# eMMC.net
KiCad netlist of a schematic drawn in Altium Designer
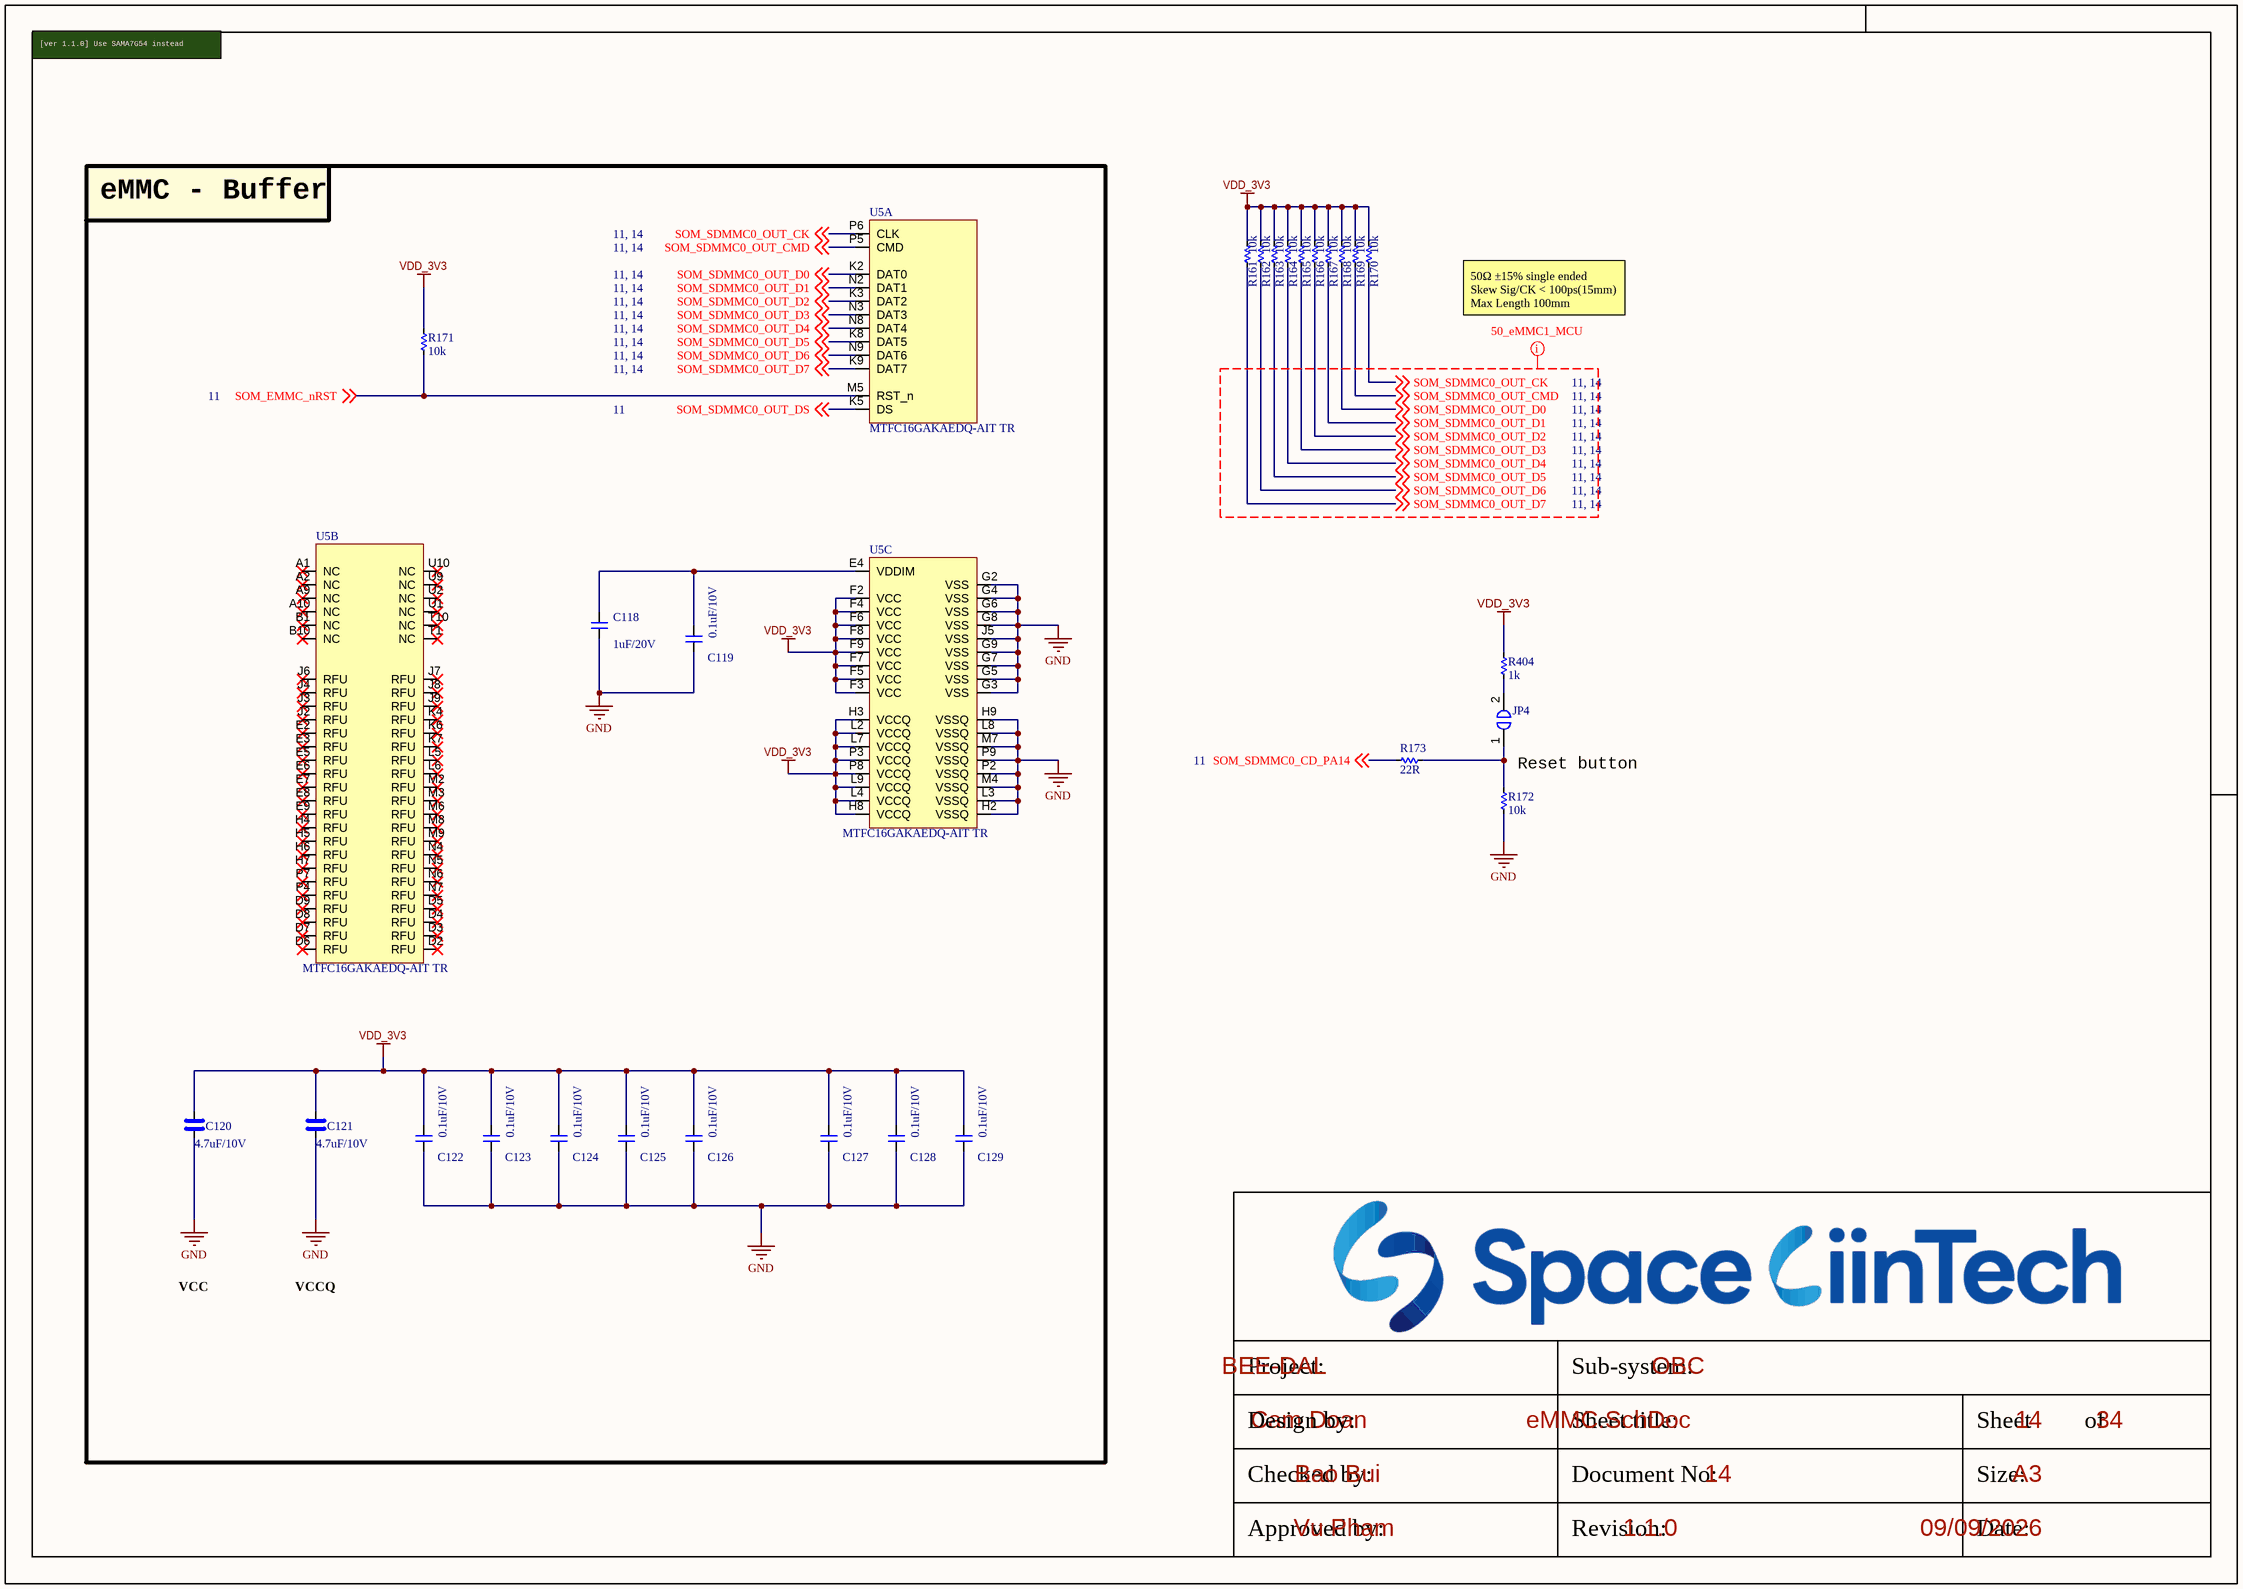
[diagram p0: eMMC.SchDoc]

(export (version "E")
  (design (tool "Eeschema 10.0.6"))
  (components
    (comp (ref "C118")
      (value "1uF/20V")
      (footprint "CAP_C_1005X50_L")
      (description "CAP CHIP")
      (libsource (lib "IFBschelib") (part "_CAP_C_2"))
    )
    (comp (ref "C119")
      (value "0.1uF/10V")
      (footprint "CAP_C_1005X50_L")
      (description "CAP")
      (libsource (lib "LABLIB") (part "_CAP_C_2"))
    )
    (comp (ref "C120")
      (value "4.7uF/10V")
      (footprint "CAP_C_1005X50_L")
      (description "CAP")
      (libsource (lib "LABLIB") (part "_CAP_C_High_2"))
    )
    (comp (ref "C121")
      (value "4.7uF/10V")
      (footprint "CAP_C_1005X50_L")
      (description "CAP")
      (libsource (lib "LABLIB") (part "_CAP_C_High_2"))
    )
    (comp (ref "C122")
      (value "0.1uF/10V")
      (footprint "CAP_C_1005X50_L")
      (description "CAP")
      (libsource (lib "LABLIB") (part "_CAP_C_2"))
    )
    (comp (ref "C123")
      (value "0.1uF/10V")
      (footprint "CAP_C_1005X50_L")
      (description "CAP")
      (libsource (lib "LABLIB") (part "_CAP_C_2"))
    )
    (comp (ref "C124")
      (value "0.1uF/10V")
      (footprint "CAP_C_1005X50_L")
      (description "CAP")
      (libsource (lib "LABLIB") (part "_CAP_C_2"))
    )
    (comp (ref "C125")
      (value "0.1uF/10V")
      (footprint "CAP_C_1005X50_L")
      (description "CAP")
      (libsource (lib "LABLIB") (part "_CAP_C_2"))
    )
    (comp (ref "C126")
      (value "0.1uF/10V")
      (footprint "CAP_C_1005X50_L")
      (description "CAP")
      (libsource (lib "LABLIB") (part "_CAP_C_2"))
    )
    (comp (ref "C127")
      (value "0.1uF/10V")
      (footprint "CAP_C_1005X50_L")
      (description "CAP")
      (libsource (lib "LABLIB") (part "_CAP_C_2"))
    )
    (comp (ref "C128")
      (value "0.1uF/10V")
      (footprint "CAP_C_1005X50_L")
      (description "CAP")
      (libsource (lib "LABLIB") (part "_CAP_C_2"))
    )
    (comp (ref "C129")
      (value "0.1uF/10V")
      (footprint "CAP_C_1005X50_L")
      (description "CAP")
      (libsource (lib "LABLIB") (part "_CAP_C_2"))
    )
    (comp (ref "JP4") (value "~") (footprint "JUMPER_1608") (libsource (lib "LABLIB") (part "JUMPER_1_1")))
    (comp (ref "R161")
      (value "10k")
      (footprint "RES_C_1005x30_L")
      (description "RES")
      (libsource (lib "LABLIB") (part "_RES_B_2"))
    )
    (comp (ref "R162")
      (value "10k")
      (footprint "RES_C_1005x30_L")
      (description "RES")
      (libsource (lib "LABLIB") (part "_RES_B_2"))
    )
    (comp (ref "R163")
      (value "10k")
      (footprint "RES_C_1005x30_L")
      (description "RES")
      (libsource (lib "LABLIB") (part "_RES_B_2"))
    )
    (comp (ref "R164")
      (value "10k")
      (footprint "RES_C_1005x30_L")
      (description "RES")
      (libsource (lib "LABLIB") (part "_RES_B_2"))
    )
    (comp (ref "R165")
      (value "10k")
      (footprint "RES_C_1005x30_L")
      (description "RES")
      (libsource (lib "LABLIB") (part "_RES_B_2"))
    )
    (comp (ref "R166")
      (value "10k")
      (footprint "RES_C_1005x30_L")
      (description "RES")
      (libsource (lib "LABLIB") (part "_RES_B_2"))
    )
    (comp (ref "R167")
      (value "10k")
      (footprint "RES_C_1005x30_L")
      (description "RES")
      (libsource (lib "LABLIB") (part "_RES_B_2"))
    )
    (comp (ref "R168")
      (value "10k")
      (footprint "RES_C_1005x30_L")
      (description "RES")
      (libsource (lib "LABLIB") (part "_RES_B_2"))
    )
    (comp (ref "R169")
      (value "10k")
      (footprint "RES_C_1005x30_L")
      (description "RES")
      (libsource (lib "LABLIB") (part "_RES_B_2"))
    )
    (comp (ref "R170")
      (value "10k")
      (footprint "RES_C_1005x30_L")
      (description "RES")
      (libsource (lib "LABLIB") (part "_RES_B_2"))
    )
    (comp (ref "R171")
      (value "10k")
      (footprint "RES_C_1005x30_L")
      (description "RES")
      (libsource (lib "LABLIB") (part "_RES_B_2"))
    )
    (comp (ref "R172")
      (value "10k")
      (footprint "RES_C_1005x30_L")
      (description "RES")
      (libsource (lib "LABLIB") (part "_RES_B_2"))
    )
    (comp (ref "R173")
      (value "22R")
      (footprint "RES_C_1005x30_L")
      (description "RES")
      (libsource (lib "LABLIB") (part "_RES_B_2"))
    )
    (comp (ref "R404")
      (value "1k")
      (footprint "RES_C_1005x30_L")
      (description "RES")
      (libsource (lib "LABLIB") (part "_RES_B_2"))
    )
    (comp (ref "U5")
      (value "MTFC16GAKAEDQ-AIT TR")
      (footprint "BGA_100_C_100P_10X17_1400X1800X150")
      (libsource (lib "LABLIB") (part "IC_eMMC_MTFC16GAKAEDQ-AIT TR"))
    )
  )
  (nets
    (net (code "1") (name "GND") (class "Default")
      (node (ref "C118") (pin "1") (pinfunction "1_1") (pintype "passive"))
      (node (ref "C119") (pin "1") (pinfunction "1_1") (pintype "passive"))
      (node (ref "C120") (pin "1") (pinfunction "1_1") (pintype "passive"))
      (node (ref "C121") (pin "1") (pinfunction "1_1") (pintype "passive"))
      (node (ref "C122") (pin "1") (pinfunction "1_1") (pintype "passive"))
      (node (ref "C123") (pin "1") (pinfunction "1_1") (pintype "passive"))
      (node (ref "C124") (pin "1") (pinfunction "1_1") (pintype "passive"))
      (node (ref "C125") (pin "1") (pinfunction "1_1") (pintype "passive"))
      (node (ref "C126") (pin "1") (pinfunction "1_1") (pintype "passive"))
      (node (ref "C127") (pin "1") (pinfunction "1_1") (pintype "passive"))
      (node (ref "C128") (pin "1") (pinfunction "1_1") (pintype "passive"))
      (node (ref "C129") (pin "1") (pinfunction "1_1") (pintype "passive"))
      (node (ref "R172") (pin "1") (pinfunction "1_1") (pintype "passive"))
      (node (ref "U5") (pin "G2") (pinfunction "VSS_G2") (pintype "passive"))
      (node (ref "U5") (pin "G3") (pinfunction "VSS_G3") (pintype "passive"))
      (node (ref "U5") (pin "G4") (pinfunction "VSS_G4") (pintype "passive"))
      (node (ref "U5") (pin "G5") (pinfunction "VSS_G5") (pintype "passive"))
      (node (ref "U5") (pin "G6") (pinfunction "VSS_G6") (pintype "passive"))
      (node (ref "U5") (pin "G7") (pinfunction "VSS_G7") (pintype "passive"))
      (node (ref "U5") (pin "G8") (pinfunction "VSS_G8") (pintype "passive"))
      (node (ref "U5") (pin "G9") (pinfunction "VSS_G9") (pintype "passive"))
      (node (ref "U5") (pin "H2") (pinfunction "VSSQ_H2") (pintype "passive"))
      (node (ref "U5") (pin "H9") (pinfunction "VSSQ_H9") (pintype "passive"))
      (node (ref "U5") (pin "J5") (pinfunction "VSS_J5") (pintype "passive"))
      (node (ref "U5") (pin "L3") (pinfunction "VSSQ_L3") (pintype "passive"))
      (node (ref "U5") (pin "L8") (pinfunction "VSSQ_L8") (pintype "passive"))
      (node (ref "U5") (pin "M4") (pinfunction "VSSQ_M4") (pintype "passive"))
      (node (ref "U5") (pin "M7") (pinfunction "VSSQ_M7") (pintype "passive"))
      (node (ref "U5") (pin "P2") (pinfunction "VSSQ_P2") (pintype "passive"))
      (node (ref "U5") (pin "P9") (pinfunction "VSSQ_P9") (pintype "passive"))
    )
    (net (code "2") (name "Net-(JP4-Pad1)") (class "Default")
      (node (ref "JP4") (pin "1") (pinfunction "1_1") (pintype "passive"))
      (node (ref "R172") (pin "2") (pinfunction "2_2") (pintype "passive"))
      (node (ref "R173") (pin "2") (pinfunction "2_2") (pintype "passive"))
    )
    (net (code "3") (name "Net-(JP4-Pad2)") (class "Default")
      (node (ref "JP4") (pin "2") (pinfunction "2_2") (pintype "passive"))
      (node (ref "R404") (pin "1") (pinfunction "1_1") (pintype "passive"))
    )
    (net (code "4") (name "Net-(U5C-VDDIM)") (class "Default")
      (node (ref "C118") (pin "2") (pinfunction "2_2") (pintype "passive"))
      (node (ref "C119") (pin "2") (pinfunction "2_2") (pintype "passive"))
      (node (ref "U5") (pin "E4") (pinfunction "VDDIM_E4") (pintype "passive"))
    )
    (net (code "5") (name "SOM_EMMC_nRST") (class "Default")
      (node (ref "R171") (pin "1") (pinfunction "1_1") (pintype "passive"))
      (node (ref "U5") (pin "M5") (pinfunction "RST_n_M5") (pintype "passive"))
    )
    (net (code "6") (name "SOM_SDMMC0_CD_PA14") (class "Default")
      (node (ref "R173") (pin "1") (pinfunction "1_1") (pintype "passive"))
    )
    (net (code "7") (name "SOM_SDMMC0_OUT_CK") (class "Default")
      (node (ref "R170") (pin "1") (pinfunction "1_1") (pintype "passive"))
      (node (ref "U5") (pin "P6") (pinfunction "CLK_P6") (pintype "passive"))
    )
    (net (code "8") (name "SOM_SDMMC0_OUT_CMD") (class "Default")
      (node (ref "R169") (pin "1") (pinfunction "1_1") (pintype "passive"))
      (node (ref "U5") (pin "P5") (pinfunction "CMD_P5") (pintype "passive"))
    )
    (net (code "9") (name "SOM_SDMMC0_OUT_D0") (class "Default")
      (node (ref "R168") (pin "1") (pinfunction "1_1") (pintype "passive"))
      (node (ref "U5") (pin "K2") (pinfunction "DAT0_K2") (pintype "passive"))
    )
    (net (code "10") (name "SOM_SDMMC0_OUT_D1") (class "Default")
      (node (ref "R167") (pin "1") (pinfunction "1_1") (pintype "passive"))
      (node (ref "U5") (pin "N2") (pinfunction "DAT1_N2") (pintype "passive"))
    )
    (net (code "11") (name "SOM_SDMMC0_OUT_D2") (class "Default")
      (node (ref "R166") (pin "1") (pinfunction "1_1") (pintype "passive"))
      (node (ref "U5") (pin "K3") (pinfunction "DAT2_K3") (pintype "passive"))
    )
    (net (code "12") (name "SOM_SDMMC0_OUT_D3") (class "Default")
      (node (ref "R165") (pin "1") (pinfunction "1_1") (pintype "passive"))
      (node (ref "U5") (pin "N3") (pinfunction "DAT3_N3") (pintype "passive"))
    )
    (net (code "13") (name "SOM_SDMMC0_OUT_D4") (class "Default")
      (node (ref "R164") (pin "1") (pinfunction "1_1") (pintype "passive"))
      (node (ref "U5") (pin "N8") (pinfunction "DAT4_N8") (pintype "passive"))
    )
    (net (code "14") (name "SOM_SDMMC0_OUT_D5") (class "Default")
      (node (ref "R163") (pin "1") (pinfunction "1_1") (pintype "passive"))
      (node (ref "U5") (pin "K8") (pinfunction "DAT5_K8") (pintype "passive"))
    )
    (net (code "15") (name "SOM_SDMMC0_OUT_D6") (class "Default")
      (node (ref "R162") (pin "1") (pinfunction "1_1") (pintype "passive"))
      (node (ref "U5") (pin "N9") (pinfunction "DAT6_N9") (pintype "passive"))
    )
    (net (code "16") (name "SOM_SDMMC0_OUT_D7") (class "Default")
      (node (ref "R161") (pin "1") (pinfunction "1_1") (pintype "passive"))
      (node (ref "U5") (pin "K9") (pinfunction "DAT7_K9") (pintype "passive"))
    )
    (net (code "17") (name "SOM_SDMMC0_OUT_DS") (class "Default")
      (node (ref "U5") (pin "K5") (pinfunction "DS_K5") (pintype "passive"))
    )
    (net (code "18") (name "VDD_3V3") (class "Default")
      (node (ref "C120") (pin "2") (pinfunction "2_2") (pintype "passive"))
      (node (ref "C121") (pin "2") (pinfunction "2_2") (pintype "passive"))
      (node (ref "C122") (pin "2") (pinfunction "2_2") (pintype "passive"))
      (node (ref "C123") (pin "2") (pinfunction "2_2") (pintype "passive"))
      (node (ref "C124") (pin "2") (pinfunction "2_2") (pintype "passive"))
      (node (ref "C125") (pin "2") (pinfunction "2_2") (pintype "passive"))
      (node (ref "C126") (pin "2") (pinfunction "2_2") (pintype "passive"))
      (node (ref "C127") (pin "2") (pinfunction "2_2") (pintype "passive"))
      (node (ref "C128") (pin "2") (pinfunction "2_2") (pintype "passive"))
      (node (ref "C129") (pin "2") (pinfunction "2_2") (pintype "passive"))
      (node (ref "R161") (pin "2") (pinfunction "2_2") (pintype "passive"))
      (node (ref "R162") (pin "2") (pinfunction "2_2") (pintype "passive"))
      (node (ref "R163") (pin "2") (pinfunction "2_2") (pintype "passive"))
      (node (ref "R164") (pin "2") (pinfunction "2_2") (pintype "passive"))
      (node (ref "R165") (pin "2") (pinfunction "2_2") (pintype "passive"))
      (node (ref "R166") (pin "2") (pinfunction "2_2") (pintype "passive"))
      (node (ref "R167") (pin "2") (pinfunction "2_2") (pintype "passive"))
      (node (ref "R168") (pin "2") (pinfunction "2_2") (pintype "passive"))
      (node (ref "R169") (pin "2") (pinfunction "2_2") (pintype "passive"))
      (node (ref "R170") (pin "2") (pinfunction "2_2") (pintype "passive"))
      (node (ref "R171") (pin "2") (pinfunction "2_2") (pintype "passive"))
      (node (ref "R404") (pin "2") (pinfunction "2_2") (pintype "passive"))
      (node (ref "U5") (pin "F2") (pinfunction "VCC_F2") (pintype "passive"))
      (node (ref "U5") (pin "F3") (pinfunction "VCC_F3") (pintype "passive"))
      (node (ref "U5") (pin "F4") (pinfunction "VCC_F4") (pintype "passive"))
      (node (ref "U5") (pin "F5") (pinfunction "VCC_F5") (pintype "passive"))
      (node (ref "U5") (pin "F6") (pinfunction "VCC_F6") (pintype "passive"))
      (node (ref "U5") (pin "F7") (pinfunction "VCC_F7") (pintype "passive"))
      (node (ref "U5") (pin "F8") (pinfunction "VCC_F8") (pintype "passive"))
      (node (ref "U5") (pin "F9") (pinfunction "VCC_F9") (pintype "passive"))
      (node (ref "U5") (pin "H3") (pinfunction "VCCQ_H3") (pintype "passive"))
      (node (ref "U5") (pin "H8") (pinfunction "VCCQ_H8") (pintype "passive"))
      (node (ref "U5") (pin "L2") (pinfunction "VCCQ_L2") (pintype "passive"))
      (node (ref "U5") (pin "L4") (pinfunction "VCCQ_L4") (pintype "passive"))
      (node (ref "U5") (pin "L7") (pinfunction "VCCQ_L7") (pintype "passive"))
      (node (ref "U5") (pin "L9") (pinfunction "VCCQ_L9") (pintype "passive"))
      (node (ref "U5") (pin "P3") (pinfunction "VCCQ_P3") (pintype "passive"))
      (node (ref "U5") (pin "P8") (pinfunction "VCCQ_P8") (pintype "passive"))
    )
    (net (code "19") (name "unconnected-(U5B-NC-PadA1)") (class "Default")
      (node (ref "U5") (pin "A1") (pinfunction "NC_A1") (pintype "passive+no_connect"))
    )
    (net (code "20") (name "unconnected-(U5B-NC-PadA2)") (class "Default")
      (node (ref "U5") (pin "A2") (pinfunction "NC_A2") (pintype "passive+no_connect"))
    )
    (net (code "21") (name "unconnected-(U5B-NC-PadA9)") (class "Default")
      (node (ref "U5") (pin "A9") (pinfunction "NC_A9") (pintype "passive+no_connect"))
    )
    (net (code "22") (name "unconnected-(U5B-NC-PadA10)") (class "Default")
      (node (ref "U5") (pin "A10") (pinfunction "NC_A10") (pintype "passive+no_connect"))
    )
    (net (code "23") (name "unconnected-(U5B-NC-PadB1)") (class "Default")
      (node (ref "U5") (pin "B1") (pinfunction "NC_B1") (pintype "passive+no_connect"))
    )
    (net (code "24") (name "unconnected-(U5B-NC-PadB10)") (class "Default")
      (node (ref "U5") (pin "B10") (pinfunction "NC_B10") (pintype "passive+no_connect"))
    )
    (net (code "25") (name "unconnected-(U5B-NC-PadT1)") (class "Default")
      (node (ref "U5") (pin "T1") (pinfunction "NC_T1") (pintype "passive+no_connect"))
    )
    (net (code "26") (name "unconnected-(U5B-NC-PadT10)") (class "Default")
      (node (ref "U5") (pin "T10") (pinfunction "NC_T10") (pintype "passive+no_connect"))
    )
    (net (code "27") (name "unconnected-(U5B-NC-PadU1)") (class "Default")
      (node (ref "U5") (pin "U1") (pinfunction "NC_U1") (pintype "passive+no_connect"))
    )
    (net (code "28") (name "unconnected-(U5B-NC-PadU2)") (class "Default")
      (node (ref "U5") (pin "U2") (pinfunction "NC_U2") (pintype "passive+no_connect"))
    )
    (net (code "29") (name "unconnected-(U5B-NC-PadU9)") (class "Default")
      (node (ref "U5") (pin "U9") (pinfunction "NC_U9") (pintype "passive+no_connect"))
    )
    (net (code "30") (name "unconnected-(U5B-NC-PadU10)") (class "Default")
      (node (ref "U5") (pin "U10") (pinfunction "NC_U10") (pintype "passive+no_connect"))
    )
    (net (code "31") (name "unconnected-(U5B-RFU-PadD2)") (class "Default")
      (node (ref "U5") (pin "D2") (pinfunction "RFU_D2") (pintype "passive+no_connect"))
    )
    (net (code "32") (name "unconnected-(U5B-RFU-PadD3)") (class "Default")
      (node (ref "U5") (pin "D3") (pinfunction "RFU_D3") (pintype "passive+no_connect"))
    )
    (net (code "33") (name "unconnected-(U5B-RFU-PadD4)") (class "Default")
      (node (ref "U5") (pin "D4") (pinfunction "RFU_D4") (pintype "passive+no_connect"))
    )
    (net (code "34") (name "unconnected-(U5B-RFU-PadD5)") (class "Default")
      (node (ref "U5") (pin "D5") (pinfunction "RFU_D5") (pintype "passive+no_connect"))
    )
    (net (code "35") (name "unconnected-(U5B-RFU-PadD6)") (class "Default")
      (node (ref "U5") (pin "D6") (pinfunction "RFU_D6") (pintype "passive+no_connect"))
    )
    (net (code "36") (name "unconnected-(U5B-RFU-PadD7)") (class "Default")
      (node (ref "U5") (pin "D7") (pinfunction "RFU_D7") (pintype "passive+no_connect"))
    )
    (net (code "37") (name "unconnected-(U5B-RFU-PadD8)") (class "Default")
      (node (ref "U5") (pin "D8") (pinfunction "RFU_D8") (pintype "passive+no_connect"))
    )
    (net (code "38") (name "unconnected-(U5B-RFU-PadD9)") (class "Default")
      (node (ref "U5") (pin "D9") (pinfunction "RFU_D9") (pintype "passive+no_connect"))
    )
    (net (code "39") (name "unconnected-(U5B-RFU-PadE2)") (class "Default")
      (node (ref "U5") (pin "E2") (pinfunction "RFU_E2") (pintype "passive+no_connect"))
    )
    (net (code "40") (name "unconnected-(U5B-RFU-PadE3)") (class "Default")
      (node (ref "U5") (pin "E3") (pinfunction "RFU_E3") (pintype "passive+no_connect"))
    )
    (net (code "41") (name "unconnected-(U5B-RFU-PadE5)") (class "Default")
      (node (ref "U5") (pin "E5") (pinfunction "RFU_E5") (pintype "passive+no_connect"))
    )
    (net (code "42") (name "unconnected-(U5B-RFU-PadE6)") (class "Default")
      (node (ref "U5") (pin "E6") (pinfunction "RFU_E6") (pintype "passive+no_connect"))
    )
    (net (code "43") (name "unconnected-(U5B-RFU-PadE7)") (class "Default")
      (node (ref "U5") (pin "E7") (pinfunction "RFU_E7") (pintype "passive+no_connect"))
    )
    (net (code "44") (name "unconnected-(U5B-RFU-PadE8)") (class "Default")
      (node (ref "U5") (pin "E8") (pinfunction "RFU_E8") (pintype "passive+no_connect"))
    )
    (net (code "45") (name "unconnected-(U5B-RFU-PadE9)") (class "Default")
      (node (ref "U5") (pin "E9") (pinfunction "RFU_E9") (pintype "passive+no_connect"))
    )
    (net (code "46") (name "unconnected-(U5B-RFU-PadH4)") (class "Default")
      (node (ref "U5") (pin "H4") (pinfunction "RFU_H4") (pintype "passive+no_connect"))
    )
    (net (code "47") (name "unconnected-(U5B-RFU-PadH5)") (class "Default")
      (node (ref "U5") (pin "H5") (pinfunction "RFU_H5") (pintype "passive+no_connect"))
    )
    (net (code "48") (name "unconnected-(U5B-RFU-PadH6)") (class "Default")
      (node (ref "U5") (pin "H6") (pinfunction "RFU_H6") (pintype "passive+no_connect"))
    )
    (net (code "49") (name "unconnected-(U5B-RFU-PadH7)") (class "Default")
      (node (ref "U5") (pin "H7") (pinfunction "RFU_H7") (pintype "passive+no_connect"))
    )
    (net (code "50") (name "unconnected-(U5B-RFU-PadJ2)") (class "Default")
      (node (ref "U5") (pin "J2") (pinfunction "RFU_J2") (pintype "passive+no_connect"))
    )
    (net (code "51") (name "unconnected-(U5B-RFU-PadJ3)") (class "Default")
      (node (ref "U5") (pin "J3") (pinfunction "RFU_J3") (pintype "passive+no_connect"))
    )
    (net (code "52") (name "unconnected-(U5B-RFU-PadJ4)") (class "Default")
      (node (ref "U5") (pin "J4") (pinfunction "RFU_J4") (pintype "passive+no_connect"))
    )
    (net (code "53") (name "unconnected-(U5B-RFU-PadJ6)") (class "Default")
      (node (ref "U5") (pin "J6") (pinfunction "RFU_J6") (pintype "passive+no_connect"))
    )
    (net (code "54") (name "unconnected-(U5B-RFU-PadJ7)") (class "Default")
      (node (ref "U5") (pin "J7") (pinfunction "RFU_J7") (pintype "passive+no_connect"))
    )
    (net (code "55") (name "unconnected-(U5B-RFU-PadJ8)") (class "Default")
      (node (ref "U5") (pin "J8") (pinfunction "RFU_J8") (pintype "passive+no_connect"))
    )
    (net (code "56") (name "unconnected-(U5B-RFU-PadJ9)") (class "Default")
      (node (ref "U5") (pin "J9") (pinfunction "RFU_J9") (pintype "passive+no_connect"))
    )
    (net (code "57") (name "unconnected-(U5B-RFU-PadK4)") (class "Default")
      (node (ref "U5") (pin "K4") (pinfunction "RFU_K4") (pintype "passive+no_connect"))
    )
    (net (code "58") (name "unconnected-(U5B-RFU-PadK6)") (class "Default")
      (node (ref "U5") (pin "K6") (pinfunction "RFU_K6") (pintype "passive+no_connect"))
    )
    (net (code "59") (name "unconnected-(U5B-RFU-PadK7)") (class "Default")
      (node (ref "U5") (pin "K7") (pinfunction "RFU_K7") (pintype "passive+no_connect"))
    )
    (net (code "60") (name "unconnected-(U5B-RFU-PadL5)") (class "Default")
      (node (ref "U5") (pin "L5") (pinfunction "RFU_L5") (pintype "passive+no_connect"))
    )
    (net (code "61") (name "unconnected-(U5B-RFU-PadL6)") (class "Default")
      (node (ref "U5") (pin "L6") (pinfunction "RFU_L6") (pintype "passive+no_connect"))
    )
    (net (code "62") (name "unconnected-(U5B-RFU-PadM2)") (class "Default")
      (node (ref "U5") (pin "M2") (pinfunction "RFU_M2") (pintype "passive+no_connect"))
    )
    (net (code "63") (name "unconnected-(U5B-RFU-PadM3)") (class "Default")
      (node (ref "U5") (pin "M3") (pinfunction "RFU_M3") (pintype "passive+no_connect"))
    )
    (net (code "64") (name "unconnected-(U5B-RFU-PadM6)") (class "Default")
      (node (ref "U5") (pin "M6") (pinfunction "RFU_M6") (pintype "passive+no_connect"))
    )
    (net (code "65") (name "unconnected-(U5B-RFU-PadM8)") (class "Default")
      (node (ref "U5") (pin "M8") (pinfunction "RFU_M8") (pintype "passive+no_connect"))
    )
    (net (code "66") (name "unconnected-(U5B-RFU-PadM9)") (class "Default")
      (node (ref "U5") (pin "M9") (pinfunction "RFU_M9") (pintype "passive+no_connect"))
    )
    (net (code "67") (name "unconnected-(U5B-RFU-PadN4)") (class "Default")
      (node (ref "U5") (pin "N4") (pinfunction "RFU_N4") (pintype "passive+no_connect"))
    )
    (net (code "68") (name "unconnected-(U5B-RFU-PadN5)") (class "Default")
      (node (ref "U5") (pin "N5") (pinfunction "RFU_N5") (pintype "passive+no_connect"))
    )
    (net (code "69") (name "unconnected-(U5B-RFU-PadN6)") (class "Default")
      (node (ref "U5") (pin "N6") (pinfunction "RFU_N6") (pintype "passive+no_connect"))
    )
    (net (code "70") (name "unconnected-(U5B-RFU-PadN7)") (class "Default")
      (node (ref "U5") (pin "N7") (pinfunction "RFU_N7") (pintype "passive+no_connect"))
    )
    (net (code "71") (name "unconnected-(U5B-RFU-PadP4)") (class "Default")
      (node (ref "U5") (pin "P4") (pinfunction "RFU_P4") (pintype "passive+no_connect"))
    )
    (net (code "72") (name "unconnected-(U5B-RFU-PadP7)") (class "Default")
      (node (ref "U5") (pin "P7") (pinfunction "RFU_P7") (pintype "passive+no_connect"))
    )
  )
)
